# MQTTButton.net
KiCad netlist of a schematic drawn in EAGLE
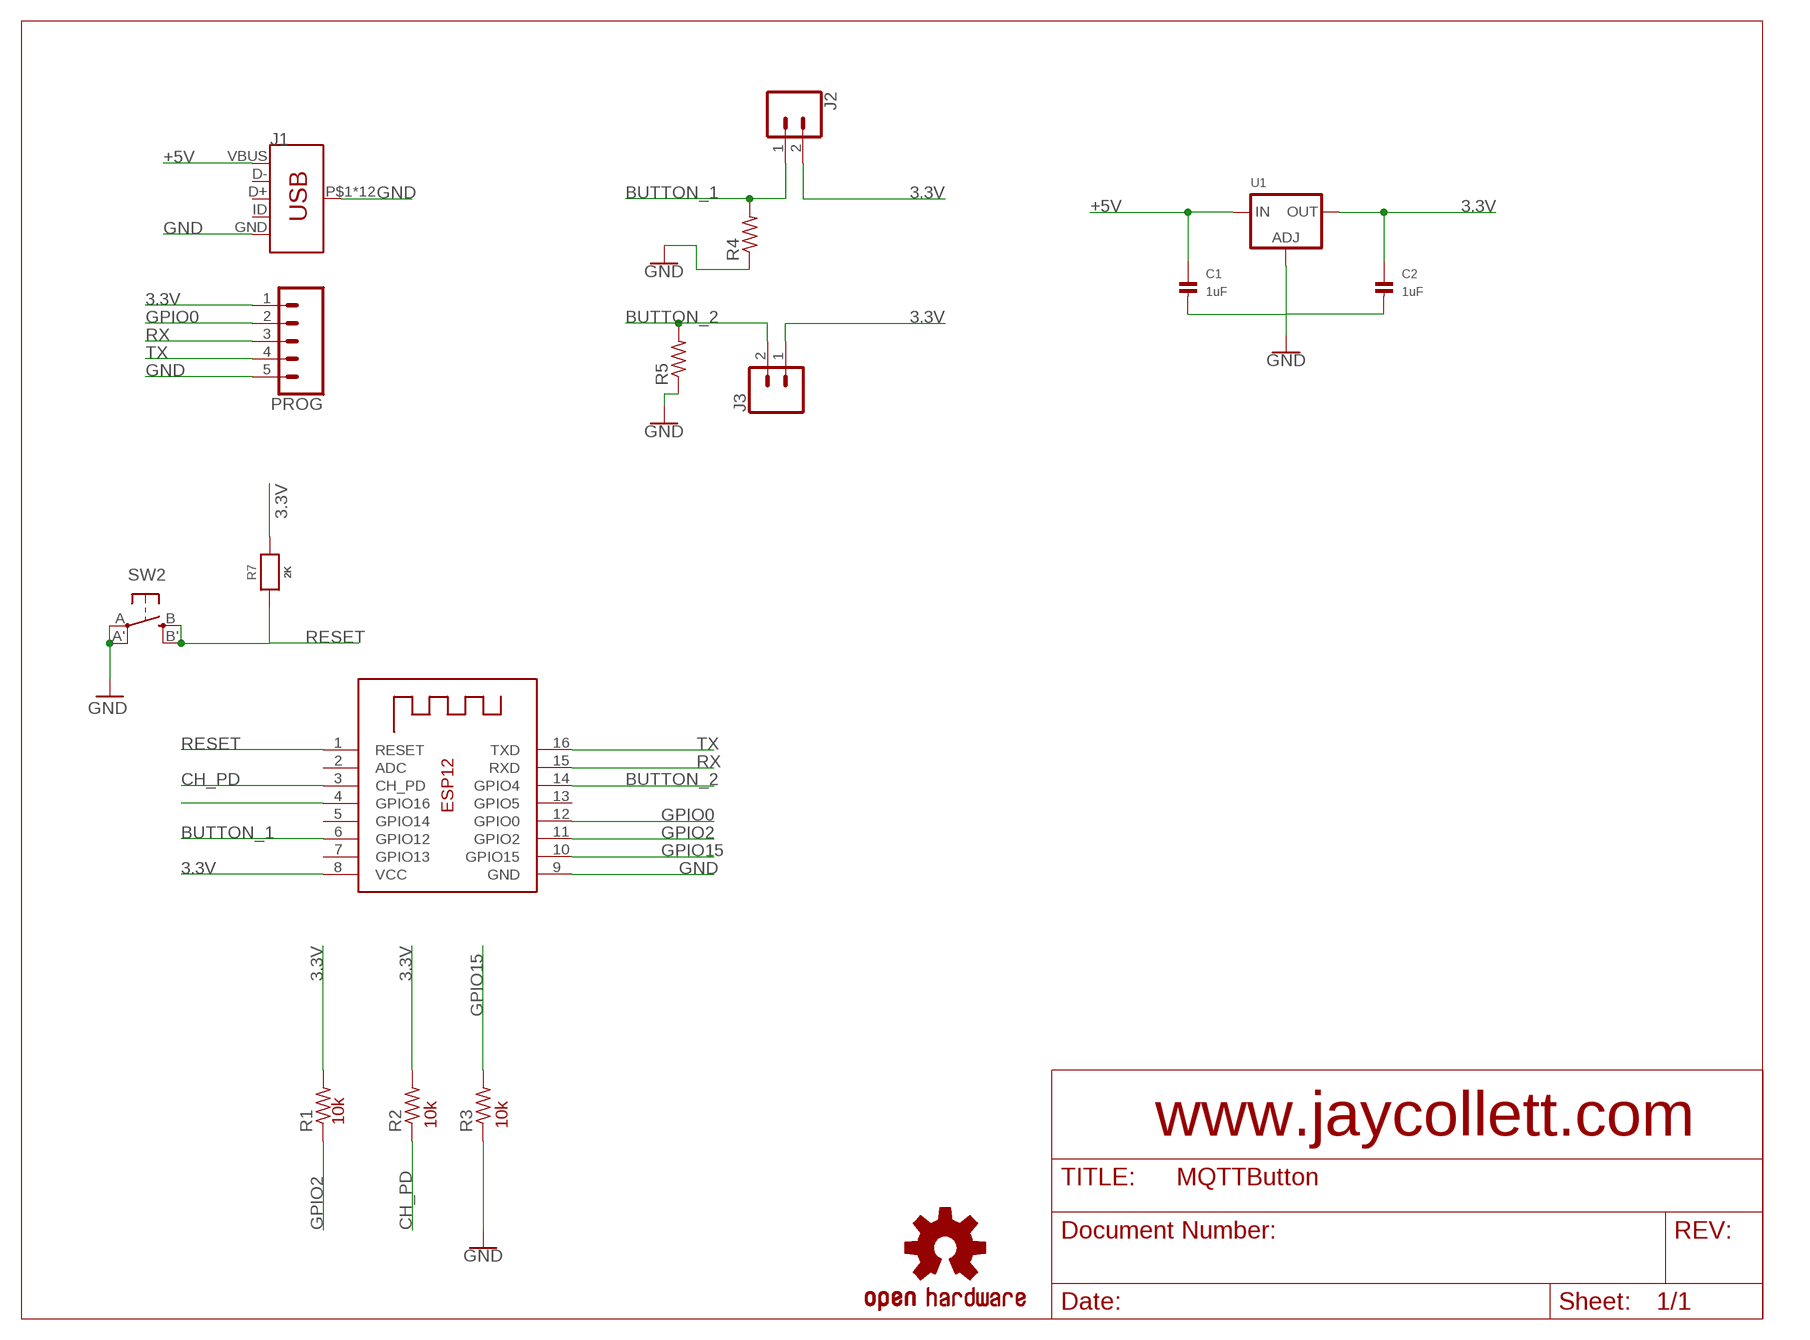
[diagram p0: schematic, sheet 1]

(export (version "E")
  (design (tool "Eeschema 10.0.6"))
  (components
    (comp (ref "C1")
      (value "1uF")
      (footprint "eagle-import:0805")
      (libsource (lib "eagle-import") (part "CAP_CERAMIC0805"))
    )
    (comp (ref "C2")
      (value "1uF")
      (footprint "eagle-import:0805")
      (libsource (lib "eagle-import") (part "CAP_CERAMIC0805"))
    )
    (comp (ref "J1")
      (value "USB_MICRO-B_HALF_PTH")
      (footprint "eagle-import:USB-MICROB-PTH")
      (libsource (lib "eagle-import") (part "USB_MICRO-B_HALF_PTH"))
    )
    (comp (ref "J2")
      (value "CONN_02LOCK")
      (footprint "eagle-import:1X02_LOCK")
      (libsource (lib "eagle-import") (part "CONN_02LOCK"))
    )
    (comp (ref "J3")
      (value "CONN_02LOCK")
      (footprint "eagle-import:1X02_LOCK")
      (libsource (lib "eagle-import") (part "CONN_02LOCK"))
    )
    (comp (ref "LOGO1")
      (value "OSHW-LOGOMINI")
      (footprint "eagle-import:OSHW-LOGO-MINI")
      (libsource (lib "eagle-import") (part "OSHW-LOGOMINI"))
    )
    (comp (ref "PROG")
      (value "CONN_05")
      (footprint "eagle-import:1X05")
      (libsource (lib "eagle-import") (part "CONN_05"))
    )
    (comp (ref "R1")
      (value "10k")
      (footprint "eagle-import:M0805")
      (libsource (lib "eagle-import") (part "R-US_M0805"))
    )
    (comp (ref "R2")
      (value "10k")
      (footprint "eagle-import:M0805")
      (libsource (lib "eagle-import") (part "R-US_M0805"))
    )
    (comp (ref "R3")
      (value "10k")
      (footprint "eagle-import:M0805")
      (libsource (lib "eagle-import") (part "R-US_M0805"))
    )
    (comp (ref "R4")
      (value "10k")
      (footprint "eagle-import:M0805")
      (libsource (lib "eagle-import") (part "R-US_M0805"))
    )
    (comp (ref "R5")
      (value "10k")
      (footprint "eagle-import:M0805")
      (libsource (lib "eagle-import") (part "R-US_M0805"))
    )
    (comp (ref "R7")
      (value "2K")
      (footprint "eagle-import:0805-NO")
      (libsource (lib "eagle-import") (part "RESISTOR0805_NOOUTLINE"))
    )
    (comp (ref "SW2")
      (value "SPST_TACT-EVQQ2")
      (footprint "eagle-import:EVQ-Q2")
      (libsource (lib "eagle-import") (part "SPST_TACT-EVQQ2"))
    )
    (comp (ref "U1")
      (value "LM1117SOT223-WAVE")
      (footprint "eagle-import:SOT223-W")
      (libsource (lib "eagle-import") (part "LM1117SOT223-WAVE"))
    )
    (comp (ref "X1")
      (value "ESP-12")
      (footprint "eagle-import:ESP-12")
      (libsource (lib "eagle-import") (part "ESP-12"))
    )
  )
  (nets
    (net (code "1") (name "/+5V") (class "Default")
      (node (ref "C1") (pin "1") (pinfunction "P$1_1") (pintype "passive"))
      (node (ref "J1") (pin "VBUS") (pinfunction "VBUS_VBUS") (pintype "power_in"))
      (node (ref "U1") (pin "3") (pinfunction "IN_3") (pintype "input"))
    )
    (net (code "2") (name "/3.3V") (class "Default")
      (node (ref "C2") (pin "1") (pinfunction "P$1_1") (pintype "passive"))
      (node (ref "J2") (pin "2") (pinfunction "2_2") (pintype "passive"))
      (node (ref "J3") (pin "1") (pinfunction "1_1") (pintype "passive"))
      (node (ref "PROG") (pin "1") (pinfunction "1_1") (pintype "passive"))
      (node (ref "R1") (pin "2") (pinfunction "2_2") (pintype "passive"))
      (node (ref "R2") (pin "2") (pinfunction "2_2") (pintype "passive"))
      (node (ref "R7") (pin "2") (pinfunction "2_2") (pintype "passive"))
      (node (ref "U1") (pin "2") (pinfunction "OUT_2") (pintype "passive"))
      (node (ref "X1") (pin "8") (pinfunction "VCC_8") (pintype "power_in"))
    )
    (net (code "3") (name "/BUTTON_1") (class "Default")
      (node (ref "J2") (pin "1") (pinfunction "1_1") (pintype "passive"))
      (node (ref "R4") (pin "2") (pinfunction "2_2") (pintype "passive"))
      (node (ref "X1") (pin "6") (pinfunction "GPIO12_6") (pintype "bidirectional"))
    )
    (net (code "4") (name "/BUTTON_2") (class "Default")
      (node (ref "J3") (pin "2") (pinfunction "2_2") (pintype "passive"))
      (node (ref "R5") (pin "2") (pinfunction "2_2") (pintype "passive"))
      (node (ref "X1") (pin "14") (pinfunction "GPIO4_14") (pintype "bidirectional"))
    )
    (net (code "5") (name "/CH_PD") (class "Default")
      (node (ref "R2") (pin "1") (pinfunction "1_1") (pintype "passive"))
      (node (ref "X1") (pin "3") (pinfunction "CH_PD_3") (pintype "input"))
    )
    (net (code "6") (name "/GPIO0") (class "Default")
      (node (ref "PROG") (pin "2") (pinfunction "2_2") (pintype "passive"))
      (node (ref "X1") (pin "12") (pinfunction "GPIO0_12") (pintype "bidirectional"))
    )
    (net (code "7") (name "/GPIO2") (class "Default")
      (node (ref "R1") (pin "1") (pinfunction "1_1") (pintype "passive"))
      (node (ref "X1") (pin "11") (pinfunction "GPIO2_11") (pintype "bidirectional"))
    )
    (net (code "8") (name "/GPIO15") (class "Default")
      (node (ref "R3") (pin "2") (pinfunction "2_2") (pintype "passive"))
      (node (ref "X1") (pin "10") (pinfunction "GPIO15_10") (pintype "bidirectional"))
    )
    (net (code "9") (name "/RESET") (class "Default")
      (node (ref "R7") (pin "1") (pinfunction "1_1") (pintype "passive"))
      (node (ref "SW2") (pin "B") (pinfunction "S_B") (pintype "passive"))
      (node (ref "SW2") (pin "B'") (pinfunction "S1_B'") (pintype "passive"))
      (node (ref "X1") (pin "1") (pinfunction "RESET_1") (pintype "input"))
    )
    (net (code "10") (name "/RX") (class "Default")
      (node (ref "PROG") (pin "3") (pinfunction "3_3") (pintype "passive"))
      (node (ref "X1") (pin "15") (pinfunction "RXD_15") (pintype "input"))
    )
    (net (code "11") (name "/TX") (class "Default")
      (node (ref "PROG") (pin "4") (pinfunction "4_4") (pintype "passive"))
      (node (ref "X1") (pin "16") (pinfunction "TXD_16") (pintype "output"))
    )
    (net (code "12") (name "GND") (class "Default")
      (node (ref "C1") (pin "2") (pinfunction "P$2_2") (pintype "passive"))
      (node (ref "C2") (pin "2") (pinfunction "P$2_2") (pintype "passive"))
      (node (ref "J1") (pin "GND") (pinfunction "GND_GND") (pintype "power_in"))
      (node (ref "J1") (pin "P$1") (pinfunction "SHIELD_P$1") (pintype "bidirectional"))
      (node (ref "J1") (pin "P$10") (pinfunction "SHIELD_P$10") (pintype "bidirectional"))
      (node (ref "J1") (pin "P$12") (pinfunction "SHIELD_P$12") (pintype "bidirectional"))
      (node (ref "J1") (pin "P$2") (pinfunction "SHIELD_P$2") (pintype "bidirectional"))
      (node (ref "J1") (pin "P$3") (pinfunction "SHIELD_P$3") (pintype "bidirectional"))
      (node (ref "J1") (pin "P$4") (pinfunction "SHIELD_P$4") (pintype "bidirectional"))
      (node (ref "J1") (pin "P$6") (pinfunction "SHIELD_P$6") (pintype "bidirectional"))
      (node (ref "J1") (pin "P$8") (pinfunction "SHIELD_P$8") (pintype "bidirectional"))
      (node (ref "J1") (pin "SHEILD2") (pinfunction "SHIELD_SHEILD2") (pintype "bidirectional"))
      (node (ref "J1") (pin "SHIELD") (pinfunction "SHIELD_SHIELD") (pintype "bidirectional"))
      (node (ref "J1") (pin "SHIELD3") (pinfunction "SHIELD_SHIELD3") (pintype "bidirectional"))
      (node (ref "J1") (pin "SHIELD4") (pinfunction "SHIELD_SHIELD4") (pintype "bidirectional"))
      (node (ref "PROG") (pin "5") (pinfunction "5_5") (pintype "passive"))
      (node (ref "R3") (pin "1") (pinfunction "1_1") (pintype "passive"))
      (node (ref "R4") (pin "1") (pinfunction "1_1") (pintype "passive"))
      (node (ref "R5") (pin "1") (pinfunction "1_1") (pintype "passive"))
      (node (ref "SW2") (pin "A") (pinfunction "P_A") (pintype "passive"))
      (node (ref "SW2") (pin "A'") (pinfunction "P1_A'") (pintype "passive"))
      (node (ref "U1") (pin "1") (pinfunction "ADJ_1") (pintype "input"))
      (node (ref "X1") (pin "9") (pinfunction "GND_9") (pintype "power_in"))
    )
    (net (code "13") (name "unconnected-(J1-PadD+)") (class "Default")
      (node (ref "J1") (pin "D+") (pinfunction "D+_D+") (pintype "bidirectional"))
    )
    (net (code "14") (name "unconnected-(J1-PadD-)") (class "Default")
      (node (ref "J1") (pin "D-") (pinfunction "D-_D-") (pintype "bidirectional"))
    )
    (net (code "15") (name "unconnected-(J1-PadID)") (class "Default")
      (node (ref "J1") (pin "ID") (pinfunction "ID_ID") (pintype "bidirectional"))
    )
    (net (code "16") (name "unconnected-(X1-ADC-Pad2)") (class "Default")
      (node (ref "X1") (pin "2") (pinfunction "ADC_2") (pintype "passive"))
    )
    (net (code "17") (name "unconnected-(X1-GPIO5-Pad13)") (class "Default")
      (node (ref "X1") (pin "13") (pinfunction "GPIO5_13") (pintype "bidirectional"))
    )
    (net (code "18") (name "unconnected-(X1-GPIO13-Pad7)") (class "Default")
      (node (ref "X1") (pin "7") (pinfunction "GPIO13_7") (pintype "bidirectional"))
    )
    (net (code "19") (name "unconnected-(X1-GPIO14-Pad5)") (class "Default")
      (node (ref "X1") (pin "5") (pinfunction "GPIO14_5") (pintype "bidirectional"))
    )
    (net (code "20") (name "unconnected-(X1-GPIO16-Pad4)") (class "Default")
      (node (ref "X1") (pin "4") (pinfunction "GPIO16_4") (pintype "bidirectional"))
    )
  )
)
